# breakout_v0_2.net
KiCad netlist of a schematic drawn in EAGLE
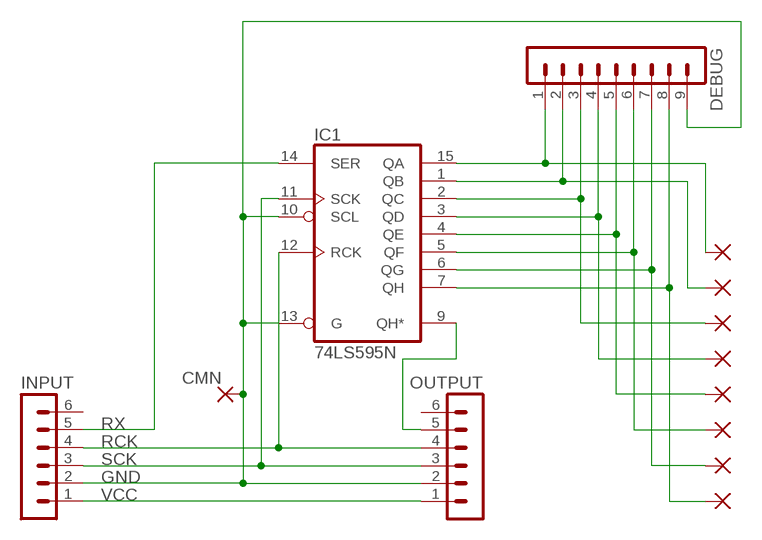
[diagram p0: schematic, sheet 1]

(export (version "E")
  (design (tool "Eeschema 10.0.6"))
  (components
    (comp (ref "CMN")
      (value "1,6/0,8")
      (footprint "eagle-import:1,6_0,8")
      (libsource (lib "eagle-import") (part "1,6/0,8"))
    )
    (comp (ref "DEBUG")
      (value "MA09-1")
      (footprint "eagle-import:MA09-1")
      (libsource (lib "eagle-import") (part "MA09-1"))
    )
    (comp (ref "DEC")
      (value "1,6/0,8")
      (footprint "eagle-import:1,6_0,8")
      (libsource (lib "eagle-import") (part "1,6/0,8"))
    )
    (comp (ref "IC1")
      (value "74LS595N")
      (footprint "eagle-import:DIL16")
      (libsource (lib "eagle-import") (part "74595NLS"))
    )
    (comp (ref "INPUT")
      (value "MA06-1")
      (footprint "eagle-import:MA06-1")
      (libsource (lib "eagle-import") (part "MA06-1"))
    )
    (comp (ref "OUTPUT")
      (value "MA06-1")
      (footprint "eagle-import:MA06-1")
      (libsource (lib "eagle-import") (part "MA06-1"))
    )
    (comp (ref "SEGA")
      (value "1,6/0,8")
      (footprint "eagle-import:1,6_0,8")
      (libsource (lib "eagle-import") (part "1,6/0,8"))
    )
    (comp (ref "SEGB")
      (value "1,6/0,8")
      (footprint "eagle-import:1,6_0,8")
      (libsource (lib "eagle-import") (part "1,6/0,8"))
    )
    (comp (ref "SEGC")
      (value "1,6/0,8")
      (footprint "eagle-import:1,6_0,8")
      (libsource (lib "eagle-import") (part "1,6/0,8"))
    )
    (comp (ref "SEGD")
      (value "1,6/0,8")
      (footprint "eagle-import:1,6_0,8")
      (libsource (lib "eagle-import") (part "1,6/0,8"))
    )
    (comp (ref "SEGE")
      (value "1,6/0,8")
      (footprint "eagle-import:1,6_0,8")
      (libsource (lib "eagle-import") (part "1,6/0,8"))
    )
    (comp (ref "SEGF")
      (value "1,6/0,8")
      (footprint "eagle-import:1,6_0,8")
      (libsource (lib "eagle-import") (part "1,6/0,8"))
    )
    (comp (ref "SEGG")
      (value "1,6/0,8")
      (footprint "eagle-import:1,6_0,8")
      (libsource (lib "eagle-import") (part "1,6/0,8"))
    )
  )
  (nets
    (net (code "1") (name "/GND") (class "Default")
      (node (ref "CMN") (pin "1") (pinfunction "P_1") (pintype "passive"))
      (node (ref "DEBUG") (pin "9") (pinfunction "9_9") (pintype "passive"))
      (node (ref "IC1") (pin "10") (pinfunction "SCL_10") (pintype "input"))
      (node (ref "IC1") (pin "13") (pinfunction "G_13") (pintype "input"))
      (node (ref "INPUT") (pin "2") (pinfunction "2_2") (pintype "passive"))
      (node (ref "OUTPUT") (pin "2") (pinfunction "2_2") (pintype "passive"))
    )
    (net (code "2") (name "/RCK") (class "Default")
      (node (ref "IC1") (pin "12") (pinfunction "RCK_12") (pintype "input"))
      (node (ref "INPUT") (pin "4") (pinfunction "4_4") (pintype "passive"))
      (node (ref "OUTPUT") (pin "4") (pinfunction "4_4") (pintype "passive"))
    )
    (net (code "3") (name "/RX") (class "Default")
      (node (ref "IC1") (pin "14") (pinfunction "SER_14") (pintype "input"))
      (node (ref "INPUT") (pin "5") (pinfunction "5_5") (pintype "passive"))
    )
    (net (code "4") (name "/SCK") (class "Default")
      (node (ref "IC1") (pin "11") (pinfunction "SCK_11") (pintype "input"))
      (node (ref "INPUT") (pin "3") (pinfunction "3_3") (pintype "passive"))
      (node (ref "OUTPUT") (pin "3") (pinfunction "3_3") (pintype "passive"))
    )
    (net (code "5") (name "/VCC") (class "Default")
      (node (ref "INPUT") (pin "1") (pinfunction "1_1") (pintype "passive"))
      (node (ref "OUTPUT") (pin "1") (pinfunction "1_1") (pintype "passive"))
    )
    (net (code "6") (name "Net-(DEC-P)") (class "Default")
      (node (ref "DEBUG") (pin "8") (pinfunction "8_8") (pintype "passive"))
      (node (ref "DEC") (pin "1") (pinfunction "P_1") (pintype "passive"))
      (node (ref "IC1") (pin "7") (pinfunction "QH_7") (pintype "tri_state"))
    )
    (net (code "7") (name "Net-(IC1A-QA)") (class "Default")
      (node (ref "DEBUG") (pin "1") (pinfunction "1_1") (pintype "passive"))
      (node (ref "IC1") (pin "15") (pinfunction "QA_15") (pintype "tri_state"))
      (node (ref "SEGA") (pin "1") (pinfunction "P_1") (pintype "passive"))
    )
    (net (code "8") (name "Net-(IC1A-QB)") (class "Default")
      (node (ref "DEBUG") (pin "2") (pinfunction "2_2") (pintype "passive"))
      (node (ref "IC1") (pin "1") (pinfunction "QB_1") (pintype "tri_state"))
      (node (ref "SEGB") (pin "1") (pinfunction "P_1") (pintype "passive"))
    )
    (net (code "9") (name "Net-(IC1A-QC)") (class "Default")
      (node (ref "DEBUG") (pin "3") (pinfunction "3_3") (pintype "passive"))
      (node (ref "IC1") (pin "2") (pinfunction "QC_2") (pintype "tri_state"))
      (node (ref "SEGC") (pin "1") (pinfunction "P_1") (pintype "passive"))
    )
    (net (code "10") (name "Net-(IC1A-QD)") (class "Default")
      (node (ref "DEBUG") (pin "4") (pinfunction "4_4") (pintype "passive"))
      (node (ref "IC1") (pin "3") (pinfunction "QD_3") (pintype "tri_state"))
      (node (ref "SEGD") (pin "1") (pinfunction "P_1") (pintype "passive"))
    )
    (net (code "11") (name "Net-(IC1A-QE)") (class "Default")
      (node (ref "DEBUG") (pin "5") (pinfunction "5_5") (pintype "passive"))
      (node (ref "IC1") (pin "4") (pinfunction "QE_4") (pintype "tri_state"))
      (node (ref "SEGE") (pin "1") (pinfunction "P_1") (pintype "passive"))
    )
    (net (code "12") (name "Net-(IC1A-QF)") (class "Default")
      (node (ref "DEBUG") (pin "6") (pinfunction "6_6") (pintype "passive"))
      (node (ref "IC1") (pin "5") (pinfunction "QF_5") (pintype "tri_state"))
      (node (ref "SEGF") (pin "1") (pinfunction "P_1") (pintype "passive"))
    )
    (net (code "13") (name "Net-(IC1A-QG)") (class "Default")
      (node (ref "DEBUG") (pin "7") (pinfunction "7_7") (pintype "passive"))
      (node (ref "IC1") (pin "6") (pinfunction "QG_6") (pintype "tri_state"))
      (node (ref "SEGG") (pin "1") (pinfunction "P_1") (pintype "passive"))
    )
    (net (code "14") (name "Net-(IC1A-QH*)") (class "Default")
      (node (ref "IC1") (pin "9") (pinfunction "QH*_9") (pintype "tri_state"))
      (node (ref "OUTPUT") (pin "5") (pinfunction "5_5") (pintype "passive"))
    )
    (net (code "15") (name "unconnected-(INPUT-Pad6)") (class "Default")
      (node (ref "INPUT") (pin "6") (pinfunction "6_6") (pintype "passive"))
    )
    (net (code "16") (name "unconnected-(OUTPUT-Pad6)") (class "Default")
      (node (ref "OUTPUT") (pin "6") (pinfunction "6_6") (pintype "passive"))
    )
  )
)
